# ContactorDrive.net
KiCad netlist of a schematic drawn in Altium Designer
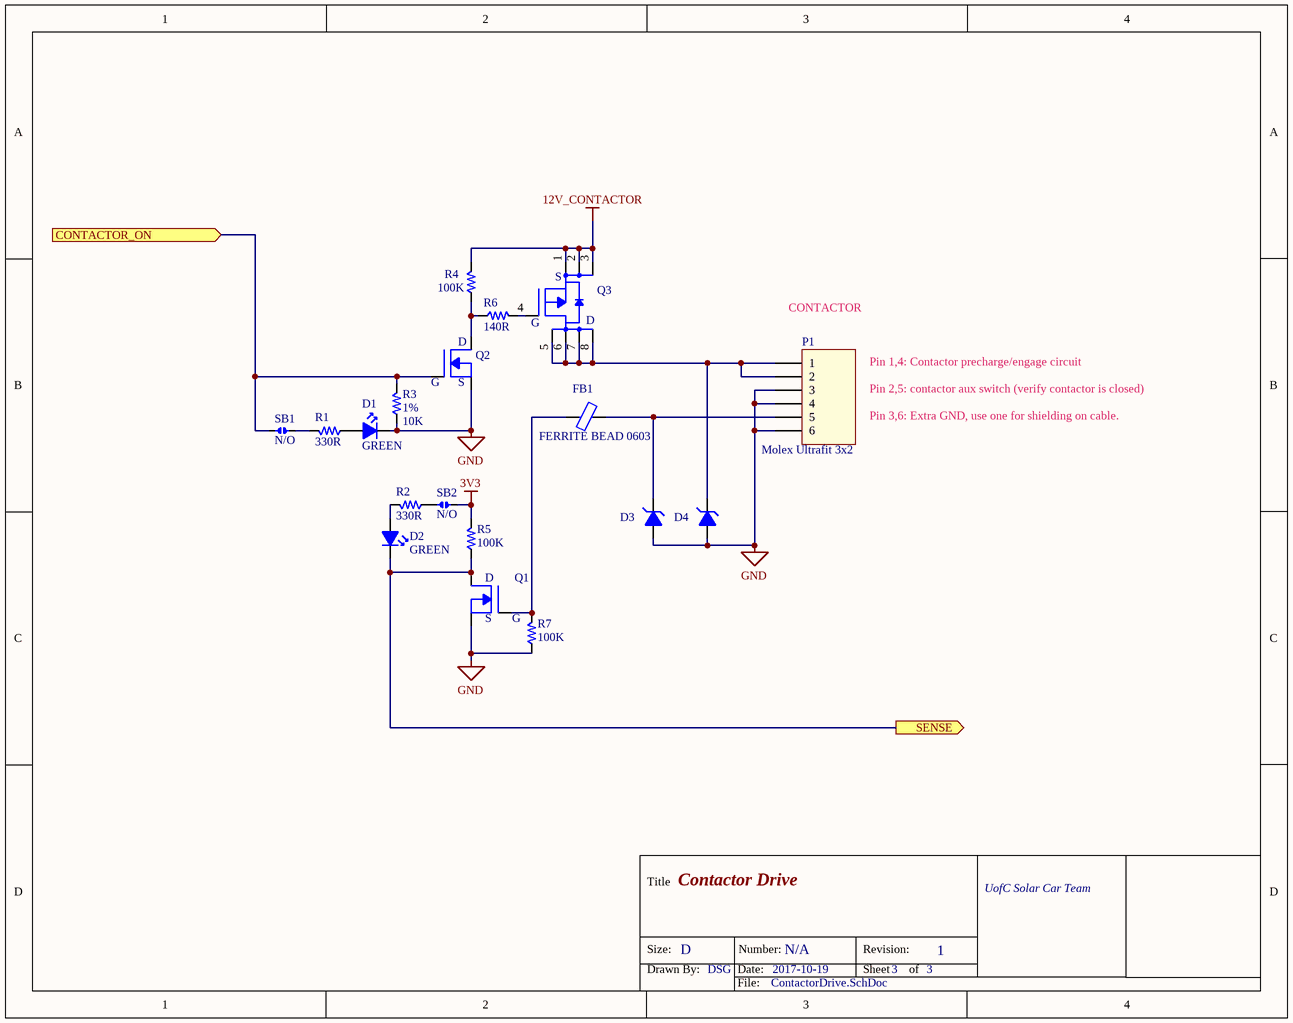
[diagram p0: ContactorDrive.SchDoc]

(export (version "E")
  (design (tool "Eeschema 10.0.6"))
  (components
    (comp (ref "D1")
      (value "D060-000G2-00")
      (footprint "SMD_0603_LED")
      (description "LED 0603 GREEN 3.2Vf 20mA")
      (fields (field (name "COLOR") "GREEN"))
      (libsource (lib "LED-0603") (part "D060-000G2-00"))
    )
    (comp (ref "D2")
      (value "D060-000G2-00")
      (footprint "SMD_0603_LED")
      (description "LED 0603 GREEN 3.2Vf 20mA")
      (fields (field (name "COLOR") "GREEN"))
      (libsource (lib "LED-0603") (part "D060-000G2-00"))
    )
    (comp (ref "D3")
      (value "TVS_14V_UNI")
      (footprint "SODFL370X108-2N")
      (description "TVS DIODE 14VWM 23.2VC SMF")
      (libsource (lib "TVS Diode Unidirectional 14V") (part "TVS_14V_UNI"))
    )
    (comp (ref "D4")
      (value "TVS_14V_UNI")
      (footprint "SODFL370X108-2N")
      (description "TVS DIODE 14VWM 23.2VC SMF")
      (libsource (lib "TVS Diode Unidirectional 14V") (part "TVS_14V_UNI"))
    )
    (comp (ref "FB1")
      (value "FERRITE BEAD 0603")
      (footprint "INDC1608X10N")
      (description "Ferrite Bead, 0603, 600Ohm @ 100MHz, 200mOhm DC")
      (libsource (lib "0603-FERRITE-600Ohm") (part "0603_FERRITE_600Ohm"))
    )
    (comp (ref "P1")
      (value "Molex Ultrafit 3x2")
      (footprint "Molex-Ultrafit-3x2")
      (description "Molex Ultrafit 3x2 - 172299-1206")
      (libsource (lib "Molex Ultrafit 3x2 - 172299-1206") (part "Molex-Ultrafit-3x2"))
    )
    (comp (ref "Q1")
      (value "NMOS - SSM3K333R")
      (footprint "NMOS - SSM3K333R - SOTFL95P180X88-3M")
      (description "MOSFET N CH 30V 6A 2-3Z1A")
      (libsource (lib "Toshiba NMOS - SOT23-F") (part "NMOS - SSM3K333R"))
    )
    (comp (ref "Q2")
      (value "NMOS - SSM3K333R")
      (footprint "NMOS - SSM3K333R - SOTFL95P180X88-3M")
      (description "MOSFET N CH 30V 6A 2-3Z1A")
      (libsource (lib "Toshiba NMOS - SOT23-F") (part "NMOS - SSM3K333R"))
    )
    (comp (ref "Q3")
      (value "INFINEON BSC030P03NS3 G")
      (footprint "BSC030P03NS3 G")
      (description "P-Channel 30V 25.4A (Ta), 100A (Tc) 2.5W (Ta), 125W (Tc) Surface Mount PG-TDSON-8")
      (libsource (lib "Infineon BSC030P03NS3 G - 8-PowerTDFN - PMOS") (part "BSC030P03NS3 G"))
    )
    (comp (ref "R1")
      (value "330R")
      (footprint "PCB_GENERIC_SMD_0603")
      (description "RES 0603 330ohm 5% 63mW")
      (fields (field (name "TOLERANCE") "5%") (field (name "POWER") "63mW"))
      (libsource (lib "RES-0603") (part "R060-00331-05"))
    )
    (comp (ref "R2")
      (value "330R")
      (footprint "PCB_GENERIC_SMD_0603")
      (description "RES 0603 330ohm 5% 63mW")
      (fields (field (name "TOLERANCE") "5%") (field (name "POWER") "63mW"))
      (libsource (lib "RES-0603") (part "R060-00331-05"))
    )
    (comp (ref "R3")
      (value "10K")
      (footprint "PCB_GENERIC_SMD_0603")
      (description "RES 0603 10K 1% 100mW")
      (fields
        (field (name "TOLERANCE") "1%")
        (field (name "POWER") "100mW")
        (field (name "Comment") "R060-00103-01")
      )
      (libsource (lib "RES-0603") (part "R060-00103-01"))
    )
    (comp (ref "R4")
      (value "100K")
      (footprint "PCB_GENERIC_SMD_0603")
      (description "RES 0603 100K 5% 63mW")
      (fields (field (name "TOLERANCE") "5%") (field (name "POWER") "63mW"))
      (libsource (lib "RES-0603") (part "R060-00104-05"))
    )
    (comp (ref "R5")
      (value "100K")
      (footprint "PCB_GENERIC_SMD_0603")
      (description "RES 0603 100K 5% 63mW")
      (fields (field (name "TOLERANCE") "5%") (field (name "POWER") "63mW"))
      (libsource (lib "RES-0603") (part "R060-00104-05"))
    )
    (comp (ref "R6")
      (value "140R")
      (footprint "PCB_GENERIC_SMD_0603")
      (description "RES 0603 140ohm 5% 63mW")
      (fields (field (name "TOLERANCE") "5%") (field (name "POWER") "63mW"))
      (libsource (lib "RES-0603") (part "R060-00141-05"))
    )
    (comp (ref "R7")
      (value "100K")
      (footprint "PCB_GENERIC_SMD_0603")
      (description "RES 0603 100K 5% 63mW")
      (fields (field (name "TOLERANCE") "5%") (field (name "POWER") "63mW"))
      (libsource (lib "RES-0603") (part "R060-00104-05"))
    )
    (comp (ref "SB1")
      (value "N/O")
      (footprint "SB_ARROW_NC")
      (description "Solder Bridge, Normally Open")
      (libsource (lib "SolderJumper20mil") (part "SB_NO"))
    )
    (comp (ref "SB2")
      (value "N/O")
      (footprint "SB_ARROW_NC")
      (description "Solder Bridge, Normally Open")
      (libsource (lib "SolderJumper20mil") (part "SB_NO"))
    )
  )
  (nets
    (net (code "1") (name "/CONTACTOR_ON") (class "Default")
      (node (ref "Q2") (pin "1") (pinfunction "G_1") (pintype "passive"))
      (node (ref "R3") (pin "2") (pinfunction "2_2") (pintype "passive"))
      (node (ref "SB1") (pin "1") (pinfunction "1_1") (pintype "passive"))
    )
    (net (code "2") (name "/SENSE") (class "Default")
      (node (ref "D2") (pin "1") (pinfunction "K_1") (pintype "passive"))
      (node (ref "Q1") (pin "3") (pinfunction "D_3") (pintype "passive"))
      (node (ref "R5") (pin "1") (pinfunction "1_1") (pintype "passive"))
    )
    (net (code "3") (name "3V3") (class "Default")
      (node (ref "R5") (pin "2") (pinfunction "2_2") (pintype "passive"))
      (node (ref "SB2") (pin "2") (pinfunction "2_2") (pintype "passive"))
    )
    (net (code "4") (name "12V_CONTACTOR") (class "Default")
      (node (ref "Q3") (pin "1") (pinfunction "S_1") (pintype "passive"))
      (node (ref "Q3") (pin "2") (pinfunction "S_2") (pintype "passive"))
      (node (ref "Q3") (pin "3") (pinfunction "S_3") (pintype "passive"))
      (node (ref "R4") (pin "2") (pinfunction "2_2") (pintype "passive"))
    )
    (net (code "5") (name "GND") (class "Default")
      (node (ref "D1") (pin "1") (pinfunction "K_1") (pintype "passive"))
      (node (ref "D3") (pin "2") (pinfunction "A_2") (pintype "passive"))
      (node (ref "D4") (pin "2") (pinfunction "A_2") (pintype "passive"))
      (node (ref "P1") (pin "3") (pinfunction "3_3") (pintype "passive"))
      (node (ref "P1") (pin "4") (pinfunction "4_4") (pintype "passive"))
      (node (ref "P1") (pin "6") (pinfunction "6_6") (pintype "passive"))
      (node (ref "Q1") (pin "2") (pinfunction "S_2") (pintype "passive"))
      (node (ref "Q2") (pin "2") (pinfunction "S_2") (pintype "passive"))
      (node (ref "R3") (pin "1") (pinfunction "1_1") (pintype "passive"))
      (node (ref "R7") (pin "1") (pinfunction "1_1") (pintype "passive"))
    )
    (net (code "6") (name "Net-(D1-A)") (class "Default")
      (node (ref "D1") (pin "2") (pinfunction "A_2") (pintype "passive"))
      (node (ref "R1") (pin "1") (pinfunction "1_1") (pintype "passive"))
    )
    (net (code "7") (name "Net-(D2-A)") (class "Default")
      (node (ref "D2") (pin "2") (pinfunction "A_2") (pintype "passive"))
      (node (ref "R2") (pin "2") (pinfunction "2_2") (pintype "passive"))
    )
    (net (code "8") (name "Net-(D3-C)") (class "Default")
      (node (ref "D3") (pin "1") (pinfunction "C_1") (pintype "passive"))
      (node (ref "FB1") (pin "2") (pinfunction "2_2") (pintype "passive"))
      (node (ref "P1") (pin "5") (pinfunction "5_5") (pintype "passive"))
    )
    (net (code "9") (name "Net-(D4-C)") (class "Default")
      (node (ref "D4") (pin "1") (pinfunction "C_1") (pintype "passive"))
      (node (ref "P1") (pin "1") (pinfunction "1_1") (pintype "passive"))
      (node (ref "P1") (pin "2") (pinfunction "2_2") (pintype "passive"))
      (node (ref "Q3") (pin "5") (pinfunction "D_5") (pintype "passive"))
      (node (ref "Q3") (pin "6") (pinfunction "D_6") (pintype "passive"))
      (node (ref "Q3") (pin "7") (pinfunction "D_7") (pintype "passive"))
      (node (ref "Q3") (pin "8") (pinfunction "D_8") (pintype "passive"))
    )
    (net (code "10") (name "Net-(Q1-G)") (class "Default")
      (node (ref "FB1") (pin "1") (pinfunction "1_1") (pintype "passive"))
      (node (ref "Q1") (pin "1") (pinfunction "G_1") (pintype "passive"))
      (node (ref "R7") (pin "2") (pinfunction "2_2") (pintype "passive"))
    )
    (net (code "11") (name "Net-(Q2-D)") (class "Default")
      (node (ref "Q2") (pin "3") (pinfunction "D_3") (pintype "passive"))
      (node (ref "R4") (pin "1") (pinfunction "1_1") (pintype "passive"))
      (node (ref "R6") (pin "1") (pinfunction "1_1") (pintype "passive"))
    )
    (net (code "12") (name "Net-(Q3-G)") (class "Default")
      (node (ref "Q3") (pin "4") (pinfunction "G_4") (pintype "passive"))
      (node (ref "R6") (pin "2") (pinfunction "2_2") (pintype "passive"))
    )
    (net (code "13") (name "Net-(R1-Pad2)") (class "Default")
      (node (ref "R1") (pin "2") (pinfunction "2_2") (pintype "passive"))
      (node (ref "SB1") (pin "2") (pinfunction "2_2") (pintype "passive"))
    )
    (net (code "14") (name "Net-(R2-Pad1)") (class "Default")
      (node (ref "R2") (pin "1") (pinfunction "1_1") (pintype "passive"))
      (node (ref "SB2") (pin "1") (pinfunction "1_1") (pintype "passive"))
    )
  )
)
